# Sensors.net
KiCad netlist of a schematic drawn in Altium Designer
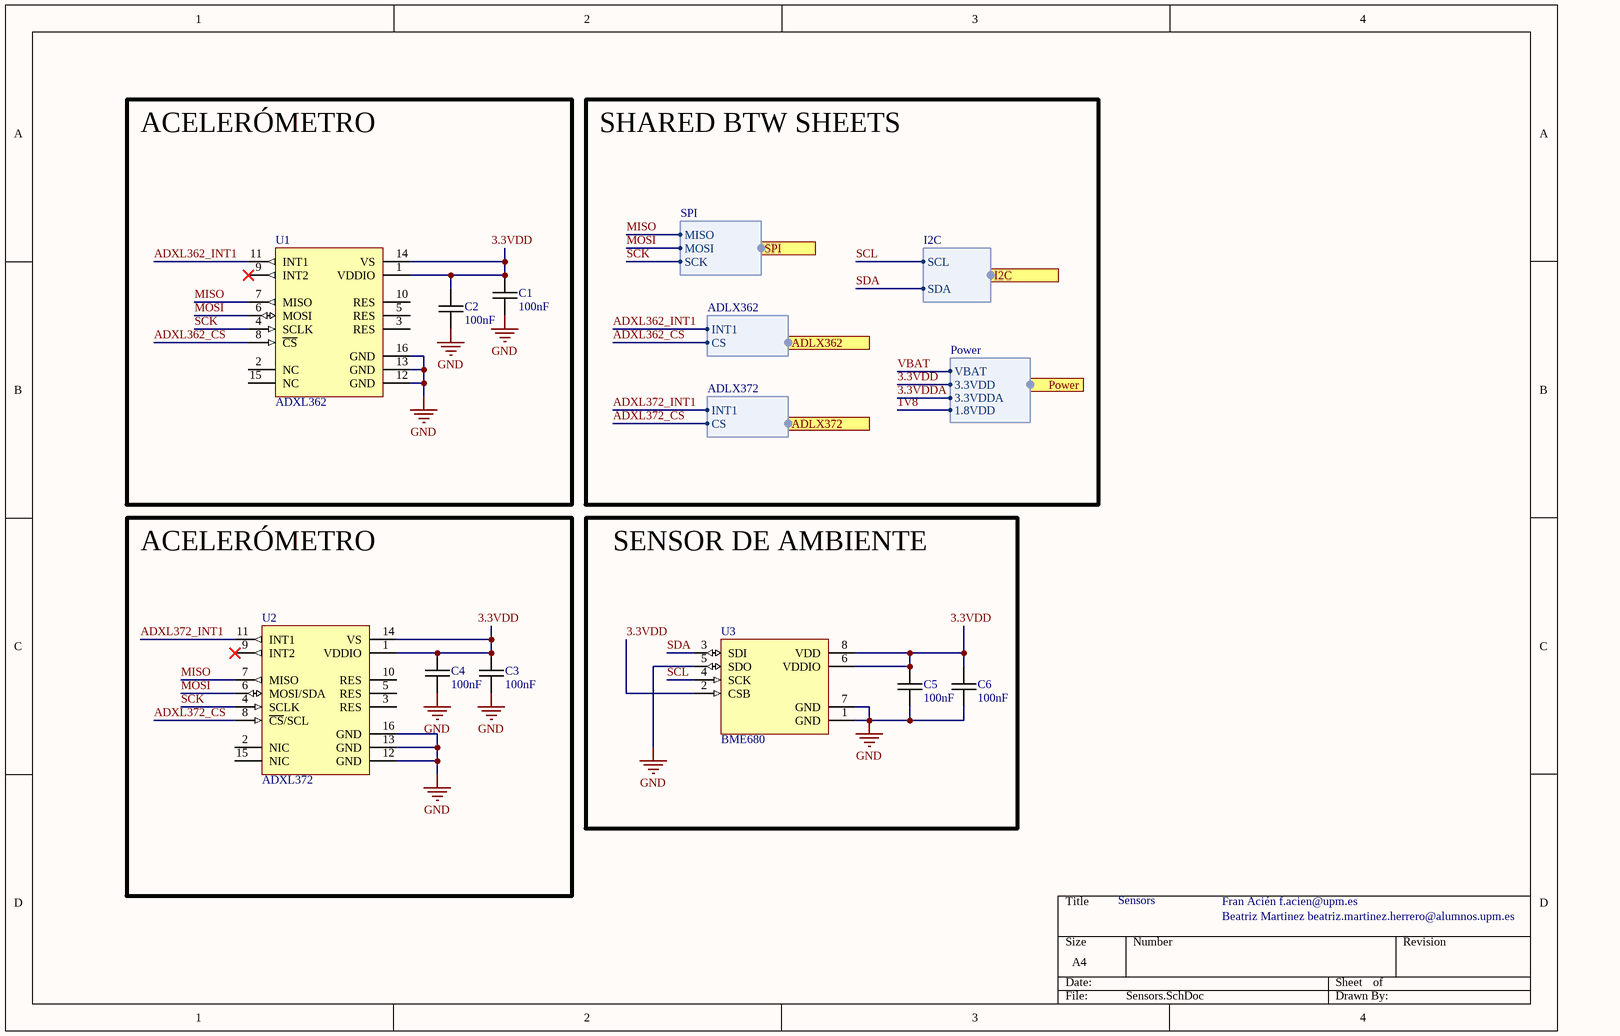
[diagram p0: Sensors.SchDoc]

(export (version "E")
  (design (tool "Eeschema 10.0.6"))
  (components
    (comp (ref "C1")
      (value "100nF")
      (footprint "0603C-GENERIC")
      (description "CAPACITOR 0603 CERAMIC")
      (fields (field (name "TOLERANCE") "±10%") (field (name "MANUFACTURER PART NUMBER") "C1608X7R1H103K"))
      (libsource (lib "vh_altium_library") (part "0603C-100NF-50V-X7R-TDK"))
    )
    (comp (ref "C2")
      (value "100nF")
      (footprint "0603C-GENERIC")
      (description "CAPACITOR 0603 CERAMIC")
      (fields (field (name "TOLERANCE") "±10%") (field (name "MANUFACTURER PART NUMBER") "C1608X7R1H103K"))
      (libsource (lib "vh_altium_library") (part "0603C-100NF-50V-X7R-TDK"))
    )
    (comp (ref "C3")
      (value "100nF")
      (footprint "0603C-GENERIC")
      (description "CAPACITOR 0603 CERAMIC")
      (fields (field (name "TOLERANCE") "±10%") (field (name "MANUFACTURER PART NUMBER") "C1608X7R1H103K"))
      (libsource (lib "vh_altium_library") (part "0603C-100NF-50V-X7R-TDK"))
    )
    (comp (ref "C4")
      (value "100nF")
      (footprint "0603C-GENERIC")
      (description "CAPACITOR 0603 CERAMIC")
      (fields (field (name "TOLERANCE") "±10%") (field (name "MANUFACTURER PART NUMBER") "C1608X7R1H103K"))
      (libsource (lib "vh_altium_library") (part "0603C-100NF-50V-X7R-TDK"))
    )
    (comp (ref "C5")
      (value "100nF")
      (footprint "0603C-GENERIC")
      (description "CAPACITOR 0603 CERAMIC")
      (fields (field (name "TOLERANCE") "±10%") (field (name "MANUFACTURER PART NUMBER") "C1608X7R1H103K"))
      (libsource (lib "vh_altium_library") (part "0603C-100NF-50V-X7R-TDK"))
    )
    (comp (ref "C6")
      (value "100nF")
      (footprint "0603C-GENERIC")
      (description "CAPACITOR 0603 CERAMIC")
      (fields (field (name "TOLERANCE") "±10%") (field (name "MANUFACTURER PART NUMBER") "C1608X7R1H103K"))
      (libsource (lib "vh_altium_library") (part "0603C-100NF-50V-X7R-TDK"))
    )
    (comp (ref "U1")
      (value "ADXL362")
      (footprint "LGA50P322X300X114-16N")
      (description "Micropower, 3-Axis, ±2 g/±4 g/±8 g Digital Output MEMS Accelerometer")
      (fields
        (field (name "MANUFACTURER") "Analog Devices")
        (field (name "PUBLISHER") "Nordic Semiconductor")
      )
      (libsource (lib "FEEL2020") (part "ADXL362"))
    )
    (comp (ref "U2")
      (value "ADXL372")
      (footprint "LGA50P322X300X114-16N")
      (description "Micropower, 3-Axis, ±200g digital output acelerometer")
      (fields
        (field (name "MANUFACTURER") "Analog Devices")
        (field (name "PUBLISHER") "Nordic Semiconductor")
      )
      (libsource (lib "FEEL2020") (part "ADXL372"))
    )
    (comp (ref "U3")
      (value "BME680")
      (footprint "BME680")
      (description "Low power gas, pressure, temperature & humidity sensor")
      (fields (field (name "MANUFACTURER") "Bosch") (field (name "PUBLISHER") "Nordic Semiconductor"))
      (libsource (lib "FEEL2020") (part "BME680"))
    )
  )
  (nets
    (net (code "7") (name "/3.3VDD") (class "Default")
      (node (ref "U3") (pin "2") (pinfunction "CSB_2") (pintype "input"))
    )
    (net (code "9") (name "/ADXL362_CS") (class "Default")
      (node (ref "U1") (pin "8") (pinfunction "~{CS}_8") (pintype "input"))
    )
    (net (code "10") (name "/ADXL362_INT1") (class "Default")
      (node (ref "U1") (pin "11") (pinfunction "INT1_11") (pintype "output"))
    )
    (net (code "11") (name "/ADXL372_CS") (class "Default")
      (node (ref "U2") (pin "8") (pinfunction "~{CS}/SCL_8") (pintype "input"))
    )
    (net (code "12") (name "/ADXL372_INT1") (class "Default")
      (node (ref "U2") (pin "11") (pinfunction "INT1_11") (pintype "output"))
    )
    (net (code "13") (name "/MISO") (class "Default")
      (node (ref "U1") (pin "7") (pinfunction "MISO_7") (pintype "output"))
      (node (ref "U2") (pin "7") (pinfunction "MISO_7") (pintype "output"))
    )
    (net (code "14") (name "/MOSI") (class "Default")
      (node (ref "U1") (pin "6") (pinfunction "MOSI_6") (pintype "bidirectional"))
      (node (ref "U2") (pin "6") (pinfunction "MOSI/SDA_6") (pintype "bidirectional"))
    )
    (net (code "15") (name "/SCK") (class "Default")
      (node (ref "U1") (pin "4") (pinfunction "SCLK_4") (pintype "input"))
      (node (ref "U2") (pin "4") (pinfunction "SCLK_4") (pintype "input"))
    )
    (net (code "16") (name "/SCL") (class "Default")
      (node (ref "U3") (pin "4") (pinfunction "SCK_4") (pintype "input"))
    )
    (net (code "17") (name "/SDA") (class "Default")
      (node (ref "U3") (pin "3") (pinfunction "SDI_3") (pintype "bidirectional"))
    )
    (net (code "24") (name "GND") (class "Default")
      (node (ref "C1") (pin "2") (pintype "passive"))
      (node (ref "C2") (pin "2") (pintype "passive"))
      (node (ref "C3") (pin "2") (pintype "passive"))
      (node (ref "C4") (pin "2") (pintype "passive"))
      (node (ref "C5") (pin "2") (pintype "passive"))
      (node (ref "C6") (pin "2") (pintype "passive"))
      (node (ref "U1") (pin "12") (pinfunction "GND_12") (pintype "power_in"))
      (node (ref "U1") (pin "13") (pinfunction "GND_13") (pintype "power_in"))
      (node (ref "U1") (pin "16") (pinfunction "GND_16") (pintype "power_in"))
      (node (ref "U2") (pin "12") (pinfunction "GND_12") (pintype "power_in"))
      (node (ref "U2") (pin "13") (pinfunction "GND_13") (pintype "power_in"))
      (node (ref "U2") (pin "16") (pinfunction "GND_16") (pintype "power_in"))
      (node (ref "U3") (pin "1") (pinfunction "GND_1") (pintype "power_in"))
      (node (ref "U3") (pin "5") (pinfunction "SDO_5") (pintype "bidirectional"))
      (node (ref "U3") (pin "7") (pinfunction "GND_7") (pintype "power_in"))
    )
    (net (code "25") (name "Net-(U1-VDDIO)") (class "Default")
      (node (ref "C1") (pin "1") (pintype "passive"))
      (node (ref "C2") (pin "1") (pintype "passive"))
      (node (ref "U1") (pin "1") (pinfunction "VDDIO_1") (pintype "power_in"))
      (node (ref "U1") (pin "14") (pinfunction "VS_14") (pintype "power_in"))
    )
    (net (code "26") (name "Net-(U2-VDDIO)") (class "Default")
      (node (ref "C3") (pin "1") (pintype "passive"))
      (node (ref "C4") (pin "1") (pintype "passive"))
      (node (ref "U2") (pin "1") (pinfunction "VDDIO_1") (pintype "power_in"))
      (node (ref "U2") (pin "14") (pinfunction "VS_14") (pintype "power_in"))
    )
    (net (code "27") (name "Net-(U3-VDD)") (class "Default")
      (node (ref "C5") (pin "1") (pintype "passive"))
      (node (ref "C6") (pin "1") (pintype "passive"))
      (node (ref "U3") (pin "6") (pinfunction "VDDIO_6") (pintype "power_in"))
      (node (ref "U3") (pin "8") (pinfunction "VDD_8") (pintype "power_in"))
    )
    (net (code "28") (name "unconnected-(U1-INT2-Pad9)") (class "Default")
      (node (ref "U1") (pin "9") (pinfunction "INT2_9") (pintype "output+no_connect"))
    )
    (net (code "29") (name "unconnected-(U1-NC-Pad2)") (class "Default")
      (node (ref "U1") (pin "2") (pinfunction "NC_2") (pintype "passive"))
    )
    (net (code "30") (name "unconnected-(U1-NC-Pad15)") (class "Default")
      (node (ref "U1") (pin "15") (pinfunction "NC_15") (pintype "passive"))
    )
    (net (code "31") (name "unconnected-(U1-RES-Pad3)") (class "Default")
      (node (ref "U1") (pin "3") (pinfunction "RES_3") (pintype "passive"))
    )
    (net (code "32") (name "unconnected-(U1-RES-Pad5)") (class "Default")
      (node (ref "U1") (pin "5") (pinfunction "RES_5") (pintype "passive"))
    )
    (net (code "33") (name "unconnected-(U1-RES-Pad10)") (class "Default")
      (node (ref "U1") (pin "10") (pinfunction "RES_10") (pintype "passive"))
    )
    (net (code "34") (name "unconnected-(U2-INT2-Pad9)") (class "Default")
      (node (ref "U2") (pin "9") (pinfunction "INT2_9") (pintype "output+no_connect"))
    )
    (net (code "35") (name "unconnected-(U2-NIC-Pad2)") (class "Default")
      (node (ref "U2") (pin "2") (pinfunction "NIC_2") (pintype "passive"))
    )
    (net (code "36") (name "unconnected-(U2-NIC-Pad15)") (class "Default")
      (node (ref "U2") (pin "15") (pinfunction "NIC_15") (pintype "passive"))
    )
    (net (code "37") (name "unconnected-(U2-RES-Pad3)") (class "Default")
      (node (ref "U2") (pin "3") (pinfunction "RES_3") (pintype "passive"))
    )
    (net (code "38") (name "unconnected-(U2-RES-Pad5)") (class "Default")
      (node (ref "U2") (pin "5") (pinfunction "RES_5") (pintype "passive"))
    )
    (net (code "39") (name "unconnected-(U2-RES-Pad10)") (class "Default")
      (node (ref "U2") (pin "10") (pinfunction "RES_10") (pintype "passive"))
    )
  )
)
